# AT89S52.net
KiCad netlist of a schematic drawn in Altium Designer
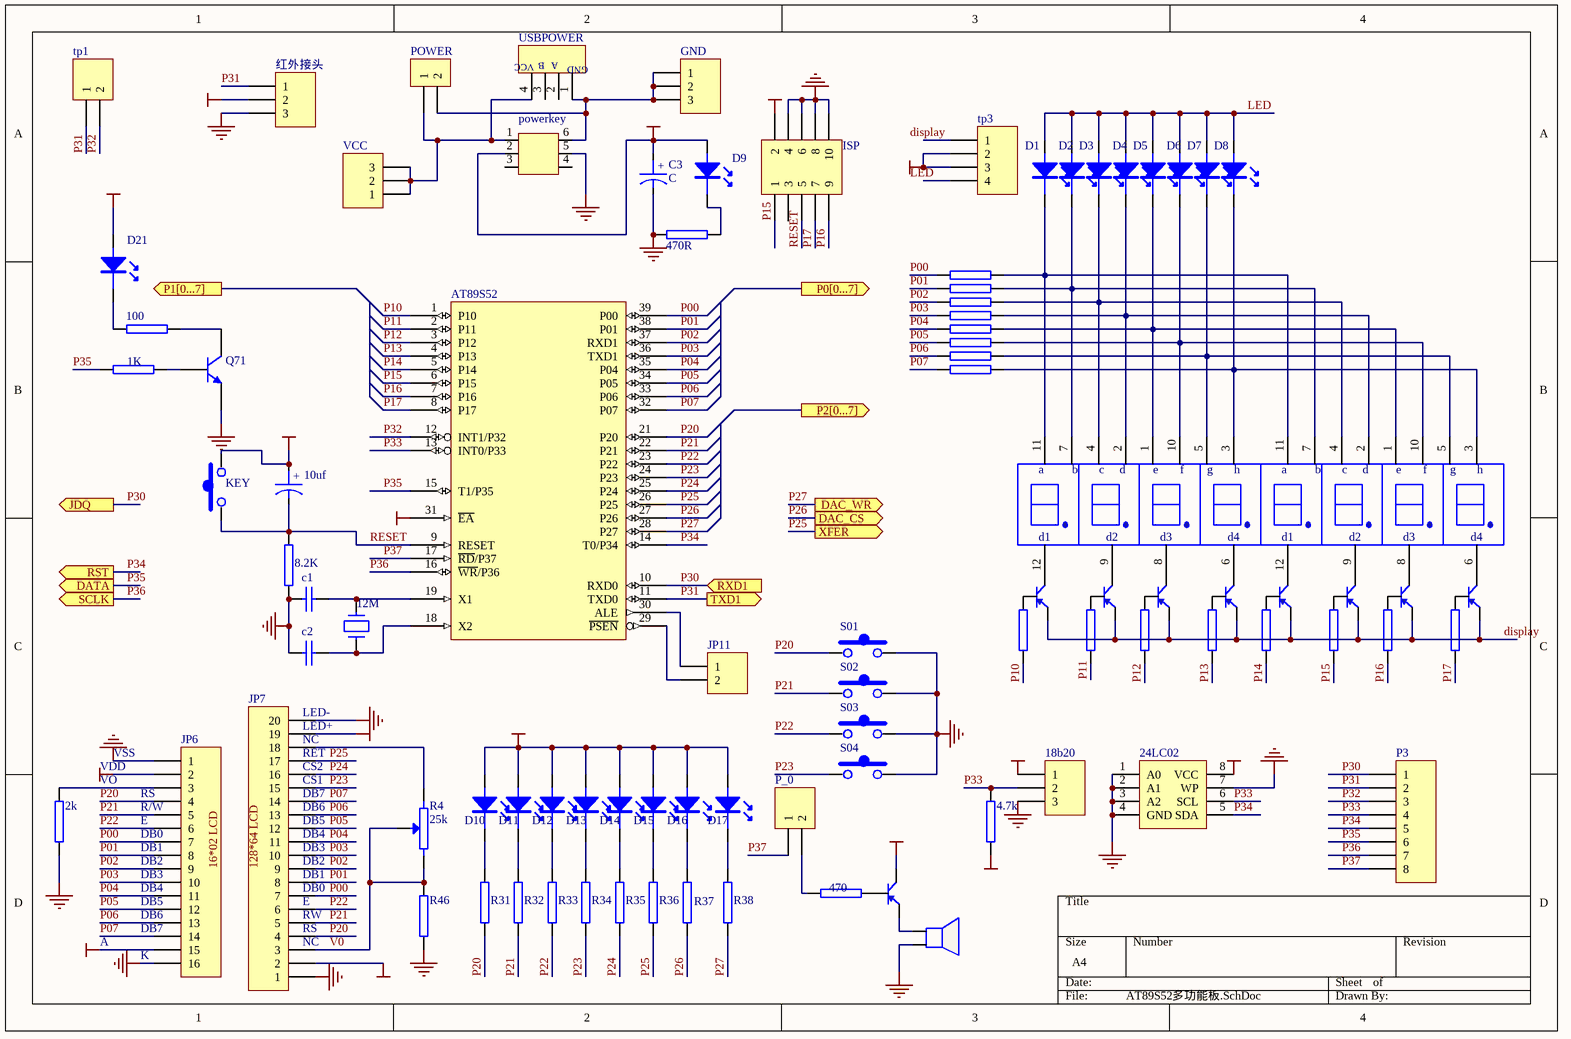
[diagram p0: AT89S52多功能板.SchDoc]

(export (version "E")
  (design (tool "Eeschema 10.0.6"))
  (components
    (comp (ref "*") (value "LS1") (footprint "LS1PF") (libsource (lib "OldCow1 (1)") (part "LS1")))
    (comp (ref "1") (value "NPN1") (footprint "NPN1PF") (libsource (lib "OldCow1 (1)") (part "NPN1")))
    (comp (ref "1K") (value "RES34") (footprint "RES1PF") (libsource (lib "") (part "RES1_1")))
    (comp (ref "2") (value "2") (footprint "NPN1PF") (libsource (lib "OldCow1 (1)") (part "NPN1")))
    (comp (ref "2k") (value "R5") (footprint "RES1PF") (libsource (lib "OldCow1 (1)") (part "RES1")))
    (comp (ref "3") (value "3") (footprint "NPN1PF") (libsource (lib "OldCow1 (1)") (part "NPN1")))
    (comp (ref "4") (value "NPN1") (footprint "NPN1PF") (libsource (lib "OldCow1 (1)") (part "NPN1")))
    (comp (ref "4.7k") (value "RES1") (footprint "RES1PF") (libsource (lib "OldCow1 (1)") (part "RES1")))
    (comp (ref "5") (value "NPN1") (footprint "NPN1PF") (libsource (lib "OldCow1 (1)") (part "NPN1")))
    (comp (ref "6") (value "NPN1") (footprint "NPN1PF") (libsource (lib "OldCow1 (1)") (part "NPN1")))
    (comp (ref "7") (value "NPN1") (footprint "NPN1PF") (libsource (lib "OldCow1 (1)") (part "NPN1")))
    (comp (ref "8") (value "NPN1") (footprint "NPN1PF") (libsource (lib "OldCow1 (1)") (part "NPN1")))
    (comp (ref "8.2K") (value "RES1") (footprint "RES1PF") (libsource (lib "") (part "RES1_1")))
    (comp (ref "10") (value "NPN1") (footprint "NPN1PF") (libsource (lib "OldCow1 (1)") (part "NPN1")))
    (comp (ref "10uf")
      (value "10uf")
      (footprint "cap2")
      (description "Capacitor")
      (libsource (lib "*") (part "CAPACITOR POL"))
    )
    (comp (ref "12M")
      (value "12M")
      (footprint "CRYSTAL")
      (description "Crystal")
      (libsource (lib "*") (part "CRYSTAL"))
    )
    (comp (ref "18b20")
      (value "CON3")
      (footprint "HDR1X3")
      (description "Header, 3-Pin")
      (fields (field (name "PUBLISHER") "Altium Limited"))
      (libsource (lib "Miscellaneous Connectors") (part "Header 3"))
    )
    (comp (ref "24LC02") (value "24LC02") (footprint "DIP8") (libsource (lib "OldCow1 (1)") (part "24LC02")))
    (comp (ref "100") (value "RES2") (footprint "RES1PF") (libsource (lib "") (part "RES1_1")))
    (comp (ref "211")
      (value "USBPOWER")
      (footprint "USBPOWER1")
      (libsource (lib "OldCow1 (1)") (part "USBPOWER"))
    )
    (comp (ref "470") (value "R2") (footprint "RES1PF") (libsource (lib "OldCow1 (1)") (part "RES1")))
    (comp (ref "470R") (value "R1") (footprint "RES1PF") (libsource (lib "OldCow1 (1)") (part "RES1")))
    (comp (ref "1111") (value "LED8") (footprint "LED8PF") (libsource (lib "OldCow1 (1)") (part "LED8")))
    (comp (ref "1112") (value "LED8") (footprint "LED8PF") (libsource (lib "OldCow1 (1)") (part "LED8")))
    (comp (ref "AT89S52")
      (value "AT89S52")
      (footprint "AT89S52PF")
      (libsource (lib "OldCow1 (1)") (part "8051"))
    )
    (comp (ref "c1")
      (value "C")
      (footprint "RAD0.3")
      (description "Capacitor")
      (libsource (lib "*") (part "CAP"))
    )
    (comp (ref "c2")
      (value "15p")
      (footprint "RAD0.3")
      (description "Capacitor")
      (libsource (lib "*") (part "CAP"))
    )
    (comp (ref "C3")
      (value "C")
      (footprint "RAD0.3")
      (description "Capacitor")
      (libsource (lib "OldCow1 (1)") (part "CAPACITOR POL"))
    )
    (comp (ref "D1") (value "LED") (footprint "RES1PF") (libsource (lib "OldCow1 (1)") (part "LED")))
    (comp (ref "D2") (value "LED") (footprint "RES1PF") (libsource (lib "OldCow1 (1)") (part "LED")))
    (comp (ref "D3") (value "LED") (footprint "RES1PF") (libsource (lib "OldCow1 (1)") (part "LED")))
    (comp (ref "D4") (value "LED") (footprint "RES1PF") (libsource (lib "OldCow1 (1)") (part "LED")))
    (comp (ref "D5") (value "LED") (footprint "RES1PF") (libsource (lib "OldCow1 (1)") (part "LED")))
    (comp (ref "D6") (value "LED") (footprint "RES1PF") (libsource (lib "OldCow1 (1)") (part "LED")))
    (comp (ref "D7") (value "LED") (footprint "RES1PF") (libsource (lib "OldCow1 (1)") (part "LED")))
    (comp (ref "D8") (value "LED") (footprint "RES1PF") (libsource (lib "OldCow1 (1)") (part "LED")))
    (comp (ref "D9") (value "LED") (footprint "RES1PF") (libsource (lib "OldCow1 (1)") (part "LED")))
    (comp (ref "D10") (value "LED") (footprint "RES1PF") (libsource (lib "OldCow1 (1)") (part "LED")))
    (comp (ref "D11") (value "LED") (footprint "RES1PF") (libsource (lib "OldCow1 (1)") (part "LED")))
    (comp (ref "D12") (value "LED") (footprint "RES1PF") (libsource (lib "OldCow1 (1)") (part "LED")))
    (comp (ref "D13") (value "LED") (footprint "RES1PF") (libsource (lib "OldCow1 (1)") (part "LED")))
    (comp (ref "D14") (value "LED") (footprint "RES1PF") (libsource (lib "OldCow1 (1)") (part "LED")))
    (comp (ref "D15") (value "LED") (footprint "RES1PF") (libsource (lib "OldCow1 (1)") (part "LED")))
    (comp (ref "D16") (value "LED") (footprint "RES1PF") (libsource (lib "OldCow1 (1)") (part "LED")))
    (comp (ref "D17") (value "LED") (footprint "RES1PF") (libsource (lib "OldCow1 (1)") (part "LED")))
    (comp (ref "D21") (value "LED") (footprint "LED") (libsource (lib "OldCow1 (1)") (part "LED")))
    (comp (ref "GND")
      (value "公共电源")
      (footprint "HDR1X3")
      (description "Header, 3-Pin")
      (fields (field (name "PUBLISHER") "Altium Limited"))
      (libsource (lib "Miscellaneous Connectors") (part "Header 3"))
    )
    (comp (ref "ISP")
      (value "download")
      (footprint "HDR2X5")
      (description "Header, 5-Pin, Dual row")
      (fields (field (name "PUBLISHER") "Altium Limited"))
      (libsource (lib "Miscellaneous Connectors") (part "Header 5X2"))
    )
    (comp (ref "JP6")
      (value "Header 16")
      (footprint "HDR1X16")
      (description "Header, 16-Pin")
      (fields (field (name "PUBLISHER") "Altium Limited"))
      (libsource (lib "Miscellaneous Connectors") (part "Header 16"))
    )
    (comp (ref "JP7")
      (value "~")
      (footprint "HDR1X20")
      (description "Header, 20-Pin")
      (fields (field (name "PUBLISHER") "Altium Limited"))
      (libsource (lib "Miscellaneous Connectors") (part "Header 20"))
    )
    (comp (ref "JP11")
      (value "Header 2")
      (footprint "HDR1X2")
      (description "Header, 2-Pin")
      (fields (field (name "PUBLISHER") "Altium Limited"))
      (libsource (lib "") (part "Header 2_1"))
    )
    (comp (ref "P3")
      (value "Header 8")
      (footprint "HDR1X8")
      (description "Header, 8-Pin")
      (fields (field (name "PUBLISHER") "Altium Limited"))
      (libsource (lib "Miscellaneous Connectors") (part "Header 8"))
    )
    (comp (ref "POWER") (value "POWER") (footprint "POWERPF") (libsource (lib "OldCow1 (1)") (part "POWER")))
    (comp (ref "powerkey")
      (value "POWERKEY")
      (footprint "POWERKEY1")
      (libsource (lib "OldCow1 (1)") (part "POWERKEY"))
    )
    (comp (ref "P_0")
      (value "Header 2")
      (footprint "HDR1X2")
      (description "Header, 2-Pin")
      (fields (field (name "PUBLISHER") "Altium Limited"))
      (libsource (lib "Miscellaneous Connectors") (part "Header 2"))
    )
    (comp (ref "Q71")
      (value "2N3904")
      (footprint "TO-92A")
      (description "NPN General Purpose Amplifier")
      (fields (field (name "PUBLISHER") "Altium Limited"))
      (libsource (lib "Miscellaneous Devices") (part "2N3904"))
    )
    (comp (ref "R4")
      (value "25k")
      (footprint "SIP3-D")
      (description "Potentiometer")
      (libsource (lib "*") (part "POT2"))
    )
    (comp (ref "R11") (value "RES1") (footprint "RES1PF") (libsource (lib "OldCow1 (1)") (part "RES1")))
    (comp (ref "R12") (value "RES1") (footprint "RES1PF") (libsource (lib "OldCow1 (1)") (part "RES1")))
    (comp (ref "R13") (value "RES1") (footprint "RES1PF") (libsource (lib "OldCow1 (1)") (part "RES1")))
    (comp (ref "R14") (value "RES1") (footprint "RES1PF") (libsource (lib "OldCow1 (1)") (part "RES1")))
    (comp (ref "R15") (value "RES1") (footprint "RES1PF") (libsource (lib "OldCow1 (1)") (part "RES1")))
    (comp (ref "R16") (value "RES1") (footprint "RES1PF") (libsource (lib "OldCow1 (1)") (part "RES1")))
    (comp (ref "R17") (value "RES1") (footprint "RES1PF") (libsource (lib "OldCow1 (1)") (part "RES1")))
    (comp (ref "R18") (value "RES1") (footprint "RES1PF") (libsource (lib "OldCow1 (1)") (part "RES1")))
    (comp (ref "R21") (value "RES1") (footprint "RES1PF") (libsource (lib "OldCow1 (1)") (part "RES1")))
    (comp (ref "R22") (value "RES1") (footprint "RES1PF") (libsource (lib "OldCow1 (1)") (part "RES1")))
    (comp (ref "R23") (value "RES1") (footprint "RES1PF") (libsource (lib "OldCow1 (1)") (part "RES1")))
    (comp (ref "R24") (value "RES1") (footprint "RES1PF") (libsource (lib "OldCow1 (1)") (part "RES1")))
    (comp (ref "R25") (value "RES1") (footprint "RES1PF") (libsource (lib "OldCow1 (1)") (part "RES1")))
    (comp (ref "R26") (value "RES1") (footprint "RES1PF") (libsource (lib "OldCow1 (1)") (part "RES1")))
    (comp (ref "R27") (value "RES1") (footprint "RES1PF") (libsource (lib "OldCow1 (1)") (part "RES1")))
    (comp (ref "R28") (value "RES1") (footprint "RES1PF") (libsource (lib "OldCow1 (1)") (part "RES1")))
    (comp (ref "R31") (value "RES1") (footprint "RES1PF") (libsource (lib "") (part "RES1_1")))
    (comp (ref "R32") (value "RES1") (footprint "RES1PF") (libsource (lib "") (part "RES1_1")))
    (comp (ref "R33") (value "RES1") (footprint "RES1PF") (libsource (lib "") (part "RES1_1")))
    (comp (ref "R34") (value "RES1") (footprint "RES1PF") (libsource (lib "") (part "RES1_1")))
    (comp (ref "R35") (value "RES1") (footprint "RES1PF") (libsource (lib "") (part "RES1_1")))
    (comp (ref "R36") (value "RES1") (footprint "RES1PF") (libsource (lib "") (part "RES1_1")))
    (comp (ref "R37") (value "RES1") (footprint "RES1PF") (libsource (lib "") (part "RES1_1")))
    (comp (ref "R38") (value "RES1") (footprint "RES1PF") (libsource (lib "") (part "RES1_1")))
    (comp (ref "R46") (value "RES1") (footprint "RES1PF") (libsource (lib "OldCow1 (1)") (part "RES1")))
    (comp (ref "reset") (value "KEY") (footprint "keypf") (libsource (lib "OldCow1 (1)") (part "KEY")))
    (comp (ref "S01") (value "KEY") (footprint "KEYPF") (libsource (lib "OldCow1 (1)") (part "KEY")))
    (comp (ref "S02") (value "KEY") (footprint "KEYPF") (libsource (lib "OldCow1 (1)") (part "KEY")))
    (comp (ref "S03") (value "KEY") (footprint "KEYPF") (libsource (lib "OldCow1 (1)") (part "KEY")))
    (comp (ref "S04") (value "KEY") (footprint "KEYPF") (libsource (lib "OldCow1 (1)") (part "KEY")))
    (comp (ref "tp1")
      (value "Header 2")
      (footprint "HDR1X2")
      (description "Header, 2-Pin")
      (fields (field (name "PUBLISHER") "Altium Limited"))
      (libsource (lib "Miscellaneous Connectors") (part "Header 2"))
    )
    (comp (ref "tp3")
      (value "Header 4")
      (footprint "HDR1X4")
      (description "Header, 4-Pin")
      (fields (field (name "PUBLISHER") "Altium Limited"))
      (libsource (lib "Miscellaneous Connectors") (part "Header 4"))
    )
    (comp (ref "VCC")
      (value "~")
      (footprint "HDR1X3")
      (description "Header, 3-Pin")
      (fields (field (name "PUBLISHER") "Altium Limited"))
      (libsource (lib "") (part "Header 3_1"))
    )
    (comp (ref "红外接头")
      (value "Header 3")
      (footprint "HDR1X3")
      (description "Header, 3-Pin")
      (fields (field (name "PUBLISHER") "Altium Limited"))
      (libsource (lib "Miscellaneous Connectors") (part "Header 3"))
    )
  )
  (nets
    (net (code "3") (name "/LED") (class "Default")
      (node (ref "D1") (pin "1") (pinfunction "A_1") (pintype "passive"))
      (node (ref "D2") (pin "1") (pinfunction "A_1") (pintype "passive"))
      (node (ref "D3") (pin "1") (pinfunction "A_1") (pintype "passive"))
      (node (ref "D4") (pin "1") (pinfunction "A_1") (pintype "passive"))
      (node (ref "D5") (pin "1") (pinfunction "A_1") (pintype "passive"))
      (node (ref "D6") (pin "1") (pinfunction "A_1") (pintype "passive"))
      (node (ref "D7") (pin "1") (pinfunction "A_1") (pintype "passive"))
      (node (ref "D8") (pin "1") (pinfunction "A_1") (pintype "passive"))
    )
    (net (code "4") (name "/P00") (class "Default")
      (node (ref "AT89S52") (pin "39") (pinfunction "P00_39") (pintype "bidirectional"))
      (node (ref "JP6") (pin "7") (pinfunction "7_7") (pintype "passive"))
      (node (ref "JP7") (pin "7") (pinfunction "7_7") (pintype "passive"))
      (node (ref "R21") (pin "1") (pinfunction "1_1") (pintype "passive"))
    )
    (net (code "6") (name "/P01") (class "Default")
      (node (ref "AT89S52") (pin "38") (pinfunction "P01_38") (pintype "bidirectional"))
      (node (ref "JP6") (pin "8") (pinfunction "8_8") (pintype "passive"))
      (node (ref "JP7") (pin "8") (pinfunction "8_8") (pintype "passive"))
      (node (ref "R22") (pin "1") (pinfunction "1_1") (pintype "passive"))
    )
    (net (code "8") (name "/P02") (class "Default")
      (node (ref "AT89S52") (pin "37") (pinfunction "RXD1_37") (pintype "bidirectional"))
      (node (ref "JP6") (pin "9") (pinfunction "9_9") (pintype "passive"))
      (node (ref "JP7") (pin "9") (pinfunction "9_9") (pintype "passive"))
      (node (ref "R23") (pin "1") (pinfunction "1_1") (pintype "passive"))
    )
    (net (code "10") (name "/P03") (class "Default")
      (node (ref "AT89S52") (pin "36") (pinfunction "TXD1_36") (pintype "bidirectional"))
      (node (ref "JP6") (pin "10") (pinfunction "10_10") (pintype "passive"))
      (node (ref "JP7") (pin "10") (pinfunction "10_10") (pintype "passive"))
      (node (ref "R24") (pin "1") (pinfunction "1_1") (pintype "passive"))
    )
    (net (code "11") (name "/P04") (class "Default")
      (node (ref "AT89S52") (pin "35") (pinfunction "P04_35") (pintype "bidirectional"))
      (node (ref "JP6") (pin "11") (pinfunction "11_11") (pintype "passive"))
      (node (ref "JP7") (pin "11") (pinfunction "11_11") (pintype "passive"))
      (node (ref "R25") (pin "1") (pinfunction "1_1") (pintype "passive"))
    )
    (net (code "12") (name "/P05") (class "Default")
      (node (ref "AT89S52") (pin "34") (pinfunction "P05_34") (pintype "bidirectional"))
      (node (ref "JP6") (pin "12") (pinfunction "12_12") (pintype "passive"))
      (node (ref "JP7") (pin "12") (pinfunction "12_12") (pintype "passive"))
      (node (ref "R26") (pin "1") (pinfunction "1_1") (pintype "passive"))
    )
    (net (code "13") (name "/P06") (class "Default")
      (node (ref "AT89S52") (pin "33") (pinfunction "P06_33") (pintype "bidirectional"))
      (node (ref "JP6") (pin "13") (pinfunction "13_13") (pintype "passive"))
      (node (ref "JP7") (pin "13") (pinfunction "13_13") (pintype "passive"))
      (node (ref "R27") (pin "1") (pinfunction "1_1") (pintype "passive"))
    )
    (net (code "14") (name "/P07") (class "Default")
      (node (ref "AT89S52") (pin "32") (pinfunction "P07_32") (pintype "bidirectional"))
      (node (ref "JP6") (pin "14") (pinfunction "14_14") (pintype "passive"))
      (node (ref "JP7") (pin "14") (pinfunction "14_14") (pintype "passive"))
      (node (ref "R28") (pin "1") (pinfunction "1_1") (pintype "passive"))
    )
    (net (code "15") (name "/P10") (class "Default")
      (node (ref "AT89S52") (pin "1") (pinfunction "P10_1") (pintype "bidirectional"))
      (node (ref "R11") (pin "1") (pinfunction "1_1") (pintype "passive"))
    )
    (net (code "16") (name "/P11") (class "Default")
      (node (ref "AT89S52") (pin "2") (pinfunction "P11_2") (pintype "bidirectional"))
      (node (ref "R12") (pin "1") (pinfunction "1_1") (pintype "passive"))
    )
    (net (code "17") (name "/P12") (class "Default")
      (node (ref "AT89S52") (pin "3") (pinfunction "P12_3") (pintype "bidirectional"))
      (node (ref "R13") (pin "1") (pinfunction "1_1") (pintype "passive"))
    )
    (net (code "18") (name "/P13") (class "Default")
      (node (ref "AT89S52") (pin "4") (pinfunction "P13_4") (pintype "bidirectional"))
      (node (ref "R14") (pin "1") (pinfunction "1_1") (pintype "passive"))
    )
    (net (code "19") (name "/P14") (class "Default")
      (node (ref "AT89S52") (pin "5") (pinfunction "P14_5") (pintype "bidirectional"))
      (node (ref "R15") (pin "1") (pinfunction "1_1") (pintype "passive"))
    )
    (net (code "20") (name "/P15") (class "Default")
      (node (ref "AT89S52") (pin "6") (pinfunction "P15_6") (pintype "bidirectional"))
      (node (ref "ISP") (pin "1") (pinfunction "1_1") (pintype "passive"))
      (node (ref "R16") (pin "1") (pinfunction "1_1") (pintype "passive"))
    )
    (net (code "21") (name "/P16") (class "Default")
      (node (ref "AT89S52") (pin "7") (pinfunction "P16_7") (pintype "bidirectional"))
      (node (ref "ISP") (pin "9") (pinfunction "9_9") (pintype "passive"))
      (node (ref "R17") (pin "1") (pinfunction "1_1") (pintype "passive"))
    )
    (net (code "22") (name "/P17") (class "Default")
      (node (ref "AT89S52") (pin "8") (pinfunction "P17_8") (pintype "bidirectional"))
      (node (ref "ISP") (pin "7") (pinfunction "7_7") (pintype "passive"))
      (node (ref "R18") (pin "1") (pinfunction "1_1") (pintype "passive"))
    )
    (net (code "23") (name "/P20") (class "Default")
      (node (ref "AT89S52") (pin "21") (pinfunction "P20_21") (pintype "bidirectional"))
      (node (ref "JP6") (pin "4") (pinfunction "4_4") (pintype "passive"))
      (node (ref "JP7") (pin "4") (pinfunction "4_4") (pintype "passive"))
      (node (ref "R31") (pin "1") (pinfunction "1_1") (pintype "passive"))
      (node (ref "S01") (pin "1") (pinfunction "1_1") (pintype "passive"))
    )
    (net (code "24") (name "/P21") (class "Default")
      (node (ref "AT89S52") (pin "22") (pinfunction "P21_22") (pintype "bidirectional"))
      (node (ref "JP6") (pin "5") (pinfunction "5_5") (pintype "passive"))
      (node (ref "JP7") (pin "5") (pinfunction "5_5") (pintype "passive"))
      (node (ref "R32") (pin "1") (pinfunction "1_1") (pintype "passive"))
      (node (ref "S02") (pin "1") (pinfunction "1_1") (pintype "passive"))
    )
    (net (code "25") (name "/P22") (class "Default")
      (node (ref "AT89S52") (pin "23") (pinfunction "P22_23") (pintype "bidirectional"))
      (node (ref "JP6") (pin "6") (pinfunction "6_6") (pintype "passive"))
      (node (ref "JP7") (pin "6") (pinfunction "6_6") (pintype "passive"))
      (node (ref "R33") (pin "1") (pinfunction "1_1") (pintype "passive"))
      (node (ref "S03") (pin "1") (pinfunction "1_1") (pintype "passive"))
    )
    (net (code "26") (name "/P23") (class "Default")
      (node (ref "AT89S52") (pin "24") (pinfunction "P23_24") (pintype "bidirectional"))
      (node (ref "JP7") (pin "15") (pinfunction "15_15") (pintype "passive"))
      (node (ref "R34") (pin "1") (pinfunction "1_1") (pintype "passive"))
      (node (ref "S04") (pin "1") (pinfunction "1_1") (pintype "passive"))
    )
    (net (code "27") (name "/P24") (class "Default")
      (node (ref "AT89S52") (pin "25") (pinfunction "P24_25") (pintype "bidirectional"))
      (node (ref "JP7") (pin "16") (pinfunction "16_16") (pintype "passive"))
      (node (ref "R35") (pin "1") (pinfunction "1_1") (pintype "passive"))
    )
    (net (code "28") (name "/P25") (class "Default")
      (node (ref "AT89S52") (pin "26") (pinfunction "P25_26") (pintype "bidirectional"))
      (node (ref "JP7") (pin "17") (pinfunction "17_17") (pintype "passive"))
      (node (ref "R36") (pin "1") (pinfunction "1_1") (pintype "passive"))
    )
    (net (code "29") (name "/P26") (class "Default")
      (node (ref "AT89S52") (pin "27") (pinfunction "P26_27") (pintype "bidirectional"))
      (node (ref "R37") (pin "1") (pinfunction "1_1") (pintype "passive"))
    )
    (net (code "30") (name "/P27") (class "Default")
      (node (ref "AT89S52") (pin "28") (pinfunction "P27_28") (pintype "bidirectional"))
      (node (ref "R38") (pin "1") (pinfunction "1_1") (pintype "passive"))
    )
    (net (code "31") (name "/P30") (class "Default")
      (node (ref "AT89S52") (pin "10") (pinfunction "RXD0_10") (pintype "bidirectional"))
      (node (ref "P3") (pin "1") (pinfunction "1_1") (pintype "passive"))
    )
    (net (code "32") (name "/P31") (class "Default")
      (node (ref "AT89S52") (pin "11") (pinfunction "TXD0_11") (pintype "bidirectional"))
      (node (ref "P3") (pin "2") (pinfunction "2_2") (pintype "passive"))
      (node (ref "tp1") (pin "1") (pinfunction "1_1") (pintype "passive"))
      (node (ref "红外接头") (pin "1") (pinfunction "1_1") (pintype "passive"))
    )
    (net (code "33") (name "/P32") (class "Default")
      (node (ref "AT89S52") (pin "12") (pinfunction "INT1/P32_12") (pintype "bidirectional"))
      (node (ref "P3") (pin "3") (pinfunction "3_3") (pintype "passive"))
      (node (ref "tp1") (pin "2") (pinfunction "2_2") (pintype "passive"))
    )
    (net (code "34") (name "/P33") (class "Default")
      (node (ref "18b20") (pin "2") (pinfunction "2_2") (pintype "passive"))
      (node (ref "24LC02") (pin "6") (pinfunction "SCL_6") (pintype "passive"))
      (node (ref "4.7k") (pin "2") (pinfunction "2_2") (pintype "passive"))
      (node (ref "AT89S52") (pin "13") (pinfunction "INT0/P33_13") (pintype "bidirectional"))
      (node (ref "P3") (pin "4") (pinfunction "4_4") (pintype "passive"))
    )
    (net (code "35") (name "/P34") (class "Default")
      (node (ref "24LC02") (pin "5") (pinfunction "SDA_5") (pintype "passive"))
      (node (ref "AT89S52") (pin "14") (pinfunction "T0/P34_14") (pintype "bidirectional"))
      (node (ref "P3") (pin "5") (pinfunction "5_5") (pintype "passive"))
    )
    (net (code "36") (name "/P35") (class "Default")
      (node (ref "1K") (pin "1") (pinfunction "1_1") (pintype "passive"))
      (node (ref "AT89S52") (pin "15") (pinfunction "T1/P35_15") (pintype "bidirectional"))
      (node (ref "P3") (pin "6") (pinfunction "6_6") (pintype "passive"))
    )
    (net (code "37") (name "/P36") (class "Default")
      (node (ref "AT89S52") (pin "16") (pinfunction "~{WR}/P36_16") (pintype "bidirectional"))
      (node (ref "P3") (pin "7") (pinfunction "7_7") (pintype "passive"))
    )
    (net (code "38") (name "/P37") (class "Default")
      (node (ref "AT89S52") (pin "17") (pinfunction "~{RD}/P37_17") (pintype "input"))
      (node (ref "P3") (pin "8") (pinfunction "8_8") (pintype "passive"))
      (node (ref "P_0") (pin "1") (pinfunction "1_1") (pintype "passive"))
    )
    (net (code "39") (name "/RESET") (class "Default")
      (node (ref "10uf") (pin "2") (pinfunction "2_2") (pintype "passive"))
      (node (ref "8.2K") (pin "1") (pinfunction "1_1") (pintype "passive"))
      (node (ref "AT89S52") (pin "9") (pinfunction "RESET_9") (pintype "input"))
      (node (ref "ISP") (pin "5") (pinfunction "5_5") (pintype "passive"))
      (node (ref "reset") (pin "1") (pinfunction "1_1") (pintype "passive"))
    )
    (net (code "40") (name "/V0") (class "Default")
      (node (ref "JP7") (pin "3") (pinfunction "3_3") (pintype "passive"))
      (node (ref "R4") (pin "1") (pinfunction "1_1") (pintype "passive"))
      (node (ref "R4") (pin "3") (pinfunction "W_3") (pintype "passive"))
      (node (ref "R46") (pin "2") (pinfunction "2_2") (pintype "passive"))
    )
    (net (code "41") (name "/display") (class "Default")
      (node (ref "1") (pin "e") (pinfunction "1_e") (pintype "passive"))
      (node (ref "2") (pin "e") (pinfunction "1_e") (pintype "passive"))
      (node (ref "3") (pin "e") (pinfunction "1_e") (pintype "passive"))
      (node (ref "4") (pin "e") (pinfunction "1_e") (pintype "passive"))
      (node (ref "5") (pin "e") (pinfunction "1_e") (pintype "passive"))
      (node (ref "6") (pin "e") (pinfunction "1_e") (pintype "passive"))
      (node (ref "7") (pin "e") (pinfunction "1_e") (pintype "passive"))
      (node (ref "8") (pin "e") (pinfunction "1_e") (pintype "passive"))
    )
    (net (code "42") (name "GND") (class "Default")
      (node (ref "*") (pin "2") (pinfunction "2_2") (pintype "passive"))
      (node (ref "18b20") (pin "3") (pinfunction "3_3") (pintype "passive"))
      (node (ref "24LC02") (pin "1") (pinfunction "A0_1") (pintype "passive"))
      (node (ref "24LC02") (pin "2") (pinfunction "A1_2") (pintype "passive"))
      (node (ref "24LC02") (pin "3") (pinfunction "A2_3") (pintype "passive"))
      (node (ref "24LC02") (pin "4") (pinfunction "GND_4") (pintype "passive"))
      (node (ref "24LC02") (pin "7") (pinfunction "WP_7") (pintype "passive"))
      (node (ref "2k") (pin "1") (pinfunction "1_1") (pintype "passive"))
      (node (ref "470R") (pin "2") (pinfunction "2_2") (pintype "passive"))
      (node (ref "8.2K") (pin "2") (pinfunction "2_2") (pintype "passive"))
      (node (ref "AT89S52") (pin "20") (pinfunction "GND_20") (pintype "power_in"))
      (node (ref "C3") (pin "2") (pinfunction "2_2") (pintype "passive"))
      (node (ref "ISP") (pin "10") (pinfunction "10_10") (pintype "passive"))
      (node (ref "ISP") (pin "4") (pinfunction "4_4") (pintype "passive"))
      (node (ref "ISP") (pin "6") (pinfunction "6_6") (pintype "passive"))
      (node (ref "ISP") (pin "8") (pinfunction "8_8") (pintype "passive"))
      (node (ref "JP6") (pin "1") (pinfunction "1_1") (pintype "passive"))
      (node (ref "JP6") (pin "16") (pinfunction "16_16") (pintype "passive"))
      (node (ref "JP7") (pin "1") (pinfunction "1_1") (pintype "passive"))
      (node (ref "JP7") (pin "20") (pinfunction "20_20") (pintype "passive"))
      (node (ref "Q71") (pin "1") (pinfunction "E_1") (pintype "passive"))
      (node (ref "R46") (pin "1") (pinfunction "1_1") (pintype "passive"))
      (node (ref "S01") (pin "2") (pinfunction "2_2") (pintype "passive"))
      (node (ref "S02") (pin "2") (pinfunction "2_2") (pintype "passive"))
      (node (ref "S03") (pin "2") (pinfunction "2_2") (pintype "passive"))
      (node (ref "S04") (pin "2") (pinfunction "2_2") (pintype "passive"))
      (node (ref "c1") (pin "1") (pinfunction "1_1") (pintype "passive"))
      (node (ref "c2") (pin "1") (pinfunction "1_1") (pintype "passive"))
      (node (ref "powerkey") (pin "5") (pinfunction "5_5") (pintype "passive"))
      (node (ref "红外接头") (pin "3") (pinfunction "3_3") (pintype "passive"))
    )
    (net (code "43") (name "Net-(1-2)") (class "Default")
      (node (ref "1") (pin "b") (pinfunction "2_b") (pintype "passive"))
      (node (ref "R11") (pin "2") (pinfunction "2_2") (pintype "passive"))
    )
    (net (code "44") (name "Net-(1-3)") (class "Default")
      (node (ref "1") (pin "c") (pinfunction "3_c") (pintype "passive"))
      (node (ref "1112") (pin "12") (pinfunction "d1_12") (pintype "passive"))
    )
    (net (code "45") (name "Net-(2-2)") (class "Default")
      (node (ref "2") (pin "b") (pinfunction "2_b") (pintype "passive"))
      (node (ref "R12") (pin "2") (pinfunction "2_2") (pintype "passive"))
    )
    (net (code "46") (name "Net-(2-3)") (class "Default")
      (node (ref "1112") (pin "9") (pinfunction "5_9") (pintype "passive"))
      (node (ref "2") (pin "c") (pinfunction "3_c") (pintype "passive"))
    )
    (net (code "47") (name "Net-(2k-Pad2)") (class "Default")
      (node (ref "2k") (pin "2") (pinfunction "2_2") (pintype "passive"))
      (node (ref "JP6") (pin "3") (pinfunction "3_3") (pintype "passive"))
    )
    (net (code "48") (name "Net-(3-2)") (class "Default")
      (node (ref "3") (pin "b") (pinfunction "2_b") (pintype "passive"))
      (node (ref "R13") (pin "2") (pinfunction "2_2") (pintype "passive"))
    )
    (net (code "49") (name "Net-(3-3)") (class "Default")
      (node (ref "1112") (pin "8") (pinfunction "6_8") (pintype "passive"))
      (node (ref "3") (pin "c") (pinfunction "3_c") (pintype "passive"))
    )
    (net (code "50") (name "Net-(4-2)") (class "Default")
      (node (ref "4") (pin "b") (pinfunction "2_b") (pintype "passive"))
      (node (ref "R14") (pin "2") (pinfunction "2_2") (pintype "passive"))
    )
    (net (code "51") (name "Net-(4-3)") (class "Default")
      (node (ref "1112") (pin "6") (pinfunction "6_6") (pintype "passive"))
      (node (ref "4") (pin "c") (pinfunction "3_c") (pintype "passive"))
    )
    (net (code "52") (name "Net-(5-2)") (class "Default")
      (node (ref "5") (pin "b") (pinfunction "2_b") (pintype "passive"))
      (node (ref "R15") (pin "2") (pinfunction "2_2") (pintype "passive"))
    )
    (net (code "53") (name "Net-(6-2)") (class "Default")
      (node (ref "6") (pin "b") (pinfunction "2_b") (pintype "passive"))
      (node (ref "R16") (pin "2") (pinfunction "2_2") (pintype "passive"))
    )
    (net (code "54") (name "Net-(6-3)") (class "Default")
      (node (ref "1111") (pin "9") (pinfunction "5_9") (pintype "passive"))
      (node (ref "6") (pin "c") (pinfunction "3_c") (pintype "passive"))
    )
    (net (code "55") (name "Net-(7-2)") (class "Default")
      (node (ref "7") (pin "b") (pinfunction "2_b") (pintype "passive"))
      (node (ref "R17") (pin "2") (pinfunction "2_2") (pintype "passive"))
    )
    (net (code "56") (name "Net-(7-3)") (class "Default")
      (node (ref "1111") (pin "8") (pinfunction "6_8") (pintype "passive"))
      (node (ref "7") (pin "c") (pinfunction "3_c") (pintype "passive"))
    )
    (net (code "57") (name "Net-(8-2)") (class "Default")
      (node (ref "8") (pin "b") (pinfunction "2_b") (pintype "passive"))
      (node (ref "R18") (pin "2") (pinfunction "2_2") (pintype "passive"))
    )
    (net (code "58") (name "Net-(8-3)") (class "Default")
      (node (ref "1111") (pin "6") (pinfunction "6_6") (pintype "passive"))
      (node (ref "8") (pin "c") (pinfunction "3_c") (pintype "passive"))
    )
    (net (code "59") (name "Net-(10-1)") (class "Default")
      (node (ref "*") (pin "1") (pinfunction "1_1") (pintype "passive"))
      (node (ref "10") (pin "e") (pinfunction "1_e") (pintype "passive"))
    )
    (net (code "60") (name "Net-(10-2)") (class "Default")
      (node (ref "10") (pin "b") (pinfunction "2_b") (pintype "passive"))
      (node (ref "470") (pin "1") (pinfunction "1_1") (pintype "passive"))
    )
    (net (code "61") (name "Net-(211-3)") (class "Default")
      (node (ref "211") (pin "4") (pinfunction "3_4") (pintype "passive"))
      (node (ref "POWER") (pin "1") (pinfunction "1_1") (pintype "passive"))
      (node (ref "VCC") (pin "1") (pinfunction "1_1") (pintype "passive"))
      (node (ref "VCC") (pin "2") (pinfunction "2_2") (pintype "passive"))
      (node (ref "VCC") (pin "3") (pinfunction "3_3") (pintype "passive"))
      (node (ref "powerkey") (pin "1") (pinfunction "1_1") (pintype "passive"))
    )
    (net (code "62") (name "Net-(211-VCC)") (class "Default")
      (node (ref "211") (pin "1") (pinfunction "VCC_1") (pintype "passive"))
      (node (ref "GND") (pin "1") (pinfunction "1_1") (pintype "passive"))
      (node (ref "GND") (pin "2") (pinfunction "2_2") (pintype "passive"))
      (node (ref "GND") (pin "3") (pinfunction "3_3") (pintype "passive"))
      (node (ref "POWER") (pin "2") (pinfunction "2_2") (pintype "passive"))
      (node (ref "powerkey") (pin "6") (pinfunction "6_6") (pintype "passive"))
    )
    (net (code "63") (name "Net-(470-Pad2)") (class "Default")
      (node (ref "470") (pin "2") (pinfunction "2_2") (pintype "passive"))
      (node (ref "P_0") (pin "2") (pinfunction "2_2") (pintype "passive"))
    )
    (net (code "64") (name "Net-(1111-d1)") (class "Default")
      (node (ref "1111") (pin "12") (pinfunction "d1_12") (pintype "passive"))
      (node (ref "5") (pin "c") (pinfunction "3_c") (pintype "passive"))
    )
    (net (code "65") (name "Net-(AT89S52-ALE)") (class "Default")
      (node (ref "AT89S52") (pin "30") (pinfunction "ALE_30") (pintype "output"))
      (node (ref "JP11") (pin "1") (pinfunction "1_1") (pintype "passive"))
    )
    (net (code "66") (name "Net-(AT89S52-X1)") (class "Default")
      (node (ref "12M") (pin "1") (pinfunction "1_1") (pintype "passive"))
      (node (ref "AT89S52") (pin "19") (pinfunction "X1_19") (pintype "input"))
      (node (ref "c1") (pin "2") (pinfunction "2_2") (pintype "passive"))
    )
    (net (code "67") (name "Net-(AT89S52-X2)") (class "Default")
      (node (ref "12M") (pin "2") (pinfunction "2_2") (pintype "passive"))
      (node (ref "AT89S52") (pin "18") (pinfunction "X2_18") (pintype "input"))
      (node (ref "c2") (pin "2") (pinfunction "2_2") (pintype "passive"))
    )
    (net (code "68") (name "Net-(AT89S52-~{PSEN})") (class "Default")
      (node (ref "AT89S52") (pin "29") (pinfunction "~{PSEN}_29") (pintype "output"))
      (node (ref "JP11") (pin "2") (pinfunction "2_2") (pintype "passive"))
    )
    (net (code "69") (name "Net-(D1-K)") (class "Default")
      (node (ref "1111") (pin "11") (pinfunction "11_11") (pintype "passive"))
      (node (ref "1112") (pin "11") (pinfunction "11_11") (pintype "passive"))
      (node (ref "D1") (pin "2") (pinfunction "K_2") (pintype "passive"))
      (node (ref "R21") (pin "2") (pinfunction "2_2") (pintype "passive"))
    )
    (net (code "70") (name "Net-(D2-K)") (class "Default")
      (node (ref "1111") (pin "7") (pinfunction "7_7") (pintype "passive"))
      (node (ref "1112") (pin "7") (pinfunction "7_7") (pintype "passive"))
      (node (ref "D2") (pin "2") (pinfunction "K_2") (pintype "passive"))
      (node (ref "R22") (pin "2") (pinfunction "2_2") (pintype "passive"))
    )
    (net (code "71") (name "Net-(D3-K)") (class "Default")
      (node (ref "1111") (pin "4") (pinfunction "4_4") (pintype "passive"))
      (node (ref "1112") (pin "4") (pinfunction "4_4") (pintype "passive"))
      (node (ref "D3") (pin "2") (pinfunction "K_2") (pintype "passive"))
      (node (ref "R23") (pin "2") (pinfunction "2_2") (pintype "passive"))
    )
    (net (code "72") (name "Net-(D4-K)") (class "Default")
      (node (ref "1111") (pin "2") (pinfunction "2_2") (pintype "passive"))
      (node (ref "1112") (pin "2") (pinfunction "2_2") (pintype "passive"))
      (node (ref "D4") (pin "2") (pinfunction "K_2") (pintype "passive"))
      (node (ref "R24") (pin "2") (pinfunction "2_2") (pintype "passive"))
    )
    (net (code "73") (name "Net-(D5-K)") (class "Default")
      (node (ref "1111") (pin "1") (pinfunction "1_1") (pintype "passive"))
      (node (ref "1112") (pin "1") (pinfunction "1_1") (pintype "passive"))
      (node (ref "D5") (pin "2") (pinfunction "K_2") (pintype "passive"))
      (node (ref "R25") (pin "2") (pinfunction "2_2") (pintype "passive"))
    )
    (net (code "74") (name "Net-(D6-K)") (class "Default")
      (node (ref "1111") (pin "10") (pinfunction "10_10") (pintype "passive"))
      (node (ref "1112") (pin "10") (pinfunction "10_10") (pintype "passive"))
      (node (ref "D6") (pin "2") (pinfunction "K_2") (pintype "passive"))
      (node (ref "R26") (pin "2") (pinfunction "2_2") (pintype "passive"))
    )
    (net (code "75") (name "Net-(D7-K)") (class "Default")
      (node (ref "1111") (pin "5") (pinfunction "5_5") (pintype "passive"))
      (node (ref "1112") (pin "5") (pinfunction "5_5") (pintype "passive"))
      (node (ref "D7") (pin "2") (pinfunction "K_2") (pintype "passive"))
      (node (ref "R27") (pin "2") (pinfunction "2_2") (pintype "passive"))
    )
    (net (code "76") (name "Net-(D8-K)") (class "Default")
      (node (ref "1111") (pin "3") (pinfunction "3_3") (pintype "passive"))
      (node (ref "1112") (pin "3") (pinfunction "3_3") (pintype "passive"))
      (node (ref "D8") (pin "2") (pinfunction "K_2") (pintype "passive"))
      (node (ref "R28") (pin "2") (pinfunction "2_2") (pintype "passive"))
    )
    (net (code "77") (name "Net-(D9-K)") (class "Default")
      (node (ref "470R") (pin "1") (pinfunction "1_1") (pintype "passive"))
      (node (ref "D9") (pin "2") (pinfunction "K_2") (pintype "passive"))
    )
    (net (code "78") (name "Net-(D10-K)") (class "Default")
      (node (ref "D10") (pin "2") (pinfunction "K_2") (pintype "passive"))
      (node (ref "R31") (pin "2") (pinfunction "2_2") (pintype "passive"))
    )
    (net (code "79") (name "Net-(D11-K)") (class "Default")
      (node (ref "D11") (pin "2") (pinfunction "K_2") (pintype "passive"))
      (node (ref "R32") (pin "2") (pinfunction "2_2") (pintype "passive"))
    )
    (net (code "80") (name "Net-(D12-K)") (class "Default")
      (node (ref "D12") (pin "2") (pinfunction "K_2") (pintype "passive"))
      (node (ref "R33") (pin "2") (pinfunction "2_2") (pintype "passive"))
    )
    (net (code "81") (name "Net-(D13-K)") (class "Default")
      (node (ref "D13") (pin "2") (pinfunction "K_2") (pintype "passive"))
      (node (ref "R34") (pin "2") (pinfunction "2_2") (pintype "passive"))
    )
    (net (code "82") (name "Net-(D14-K)") (class "Default")
      (node (ref "D14") (pin "2") (pinfunction "K_2") (pintype "passive"))
      (node (ref "R35") (pin "2") (pinfunction "2_2") (pintype "passive"))
    )
    (net (code "83") (name "Net-(D15-K)") (class "Default")
      (node (ref "D15") (pin "2") (pinfunction "K_2") (pintype "passive"))
      (node (ref "R36") (pin "2") (pinfunction "2_2") (pintype "passive"))
    )
    (net (code "84") (name "Net-(D16-K)") (class "Default")
      (node (ref "D16") (pin "2") (pinfunction "K_2") (pintype "passive"))
      (node (ref "R37") (pin "2") (pinfunction "2_2") (pintype "passive"))
    )
    (net (code "85") (name "Net-(D17-K)") (class "Default")
      (node (ref "D17") (pin "2") (pinfunction "K_2") (pintype "passive"))
      (node (ref "R38") (pin "2") (pinfunction "2_2") (pintype "passive"))
    )
    (net (code "86") (name "Net-(D21-K)") (class "Default")
      (node (ref "100") (pin "1") (pinfunction "1_1") (pintype "passive"))
      (node (ref "D21") (pin "2") (pinfunction "K_2") (pintype "passive"))
    )
    (net (code "87") (name "Net-(JP7-Pad18)") (class "Default")
      (node (ref "JP7") (pin "18") (pinfunction "18_18") (pintype "passive"))
      (node (ref "R4") (pin "2") (pinfunction "2_2") (pintype "passive"))
    )
    (net (code "88") (name "Net-(Q71-B)") (class "Default")
      (node (ref "1K") (pin "2") (pinfunction "2_2") (pintype "passive"))
      (node (ref "Q71") (pin "2") (pinfunction "B_2") (pintype "passive"))
    )
    (net (code "89") (name "Net-(Q71-C)") (class "Default")
      (node (ref "100") (pin "2") (pinfunction "2_2") (pintype "passive"))
      (node (ref "Q71") (pin "3") (pinfunction "C_3") (pintype "passive"))
    )
    (net (code "90") (name "VCC") (class "Default")
      (node (ref "10") (pin "c") (pinfunction "3_c") (pintype "passive"))
      (node (ref "10uf") (pin "1") (pinfunction "1_1") (pintype "passive"))
      (node (ref "18b20") (pin "1") (pinfunction "1_1") (pintype "passive"))
      (node (ref "24LC02") (pin "8") (pinfunction "VCC_8") (pintype "passive"))
      (node (ref "4.7k") (pin "1") (pinfunction "1_1") (pintype "passive"))
      (node (ref "AT89S52") (pin "31") (pinfunction "~{EA}_31") (pintype "input"))
      (node (ref "AT89S52") (pin "40") (pinfunction "VCC_40") (pintype "power_in"))
      (node (ref "C3") (pin "1") (pinfunction "1_1") (pintype "passive"))
      (node (ref "D10") (pin "1") (pinfunction "A_1") (pintype "passive"))
      (node (ref "D11") (pin "1") (pinfunction "A_1") (pintype "passive"))
      (node (ref "D12") (pin "1") (pinfunction "A_1") (pintype "passive"))
      (node (ref "D13") (pin "1") (pinfunction "A_1") (pintype "passive"))
      (node (ref "D14") (pin "1") (pinfunction "A_1") (pintype "passive"))
      (node (ref "D15") (pin "1") (pinfunction "A_1") (pintype "passive"))
      (node (ref "D16") (pin "1") (pinfunction "A_1") (pintype "passive"))
      (node (ref "D17") (pin "1") (pinfunction "A_1") (pintype "passive"))
      (node (ref "D21") (pin "1") (pinfunction "A_1") (pintype "passive"))
      (node (ref "D9") (pin "1") (pinfunction "A_1") (pintype "passive"))
      (node (ref "ISP") (pin "2") (pinfunction "2_2") (pintype "passive"))
      (node (ref "JP6") (pin "15") (pinfunction "15_15") (pintype "passive"))
      (node (ref "JP6") (pin "2") (pinfunction "2_2") (pintype "passive"))
      (node (ref "JP7") (pin "19") (pinfunction "19_19") (pintype "passive"))
      (node (ref "JP7") (pin "2") (pinfunction "2_2") (pintype "passive"))
      (node (ref "powerkey") (pin "2") (pinfunction "2_2") (pintype "passive"))
      (node (ref "reset") (pin "2") (pinfunction "2_2") (pintype "passive"))
      (node (ref "tp3") (pin "2") (pinfunction "2_2") (pintype "passive"))
      (node (ref "tp3") (pin "3") (pinfunction "3_3") (pintype "passive"))
      (node (ref "红外接头") (pin "2") (pinfunction "2_2") (pintype "passive"))
    )
    (net (code "91") (name "unconnected-(211-2-Pad3)") (class "Default")
      (node (ref "211") (pin "3") (pinfunction "2_3") (pintype "passive"))
    )
    (net (code "92") (name "unconnected-(211-Pad2)") (class "Default")
      (node (ref "211") (pin "2") (pinfunction "2_2") (pintype "passive"))
    )
    (net (code "93") (name "unconnected-(ISP-Pad3)") (class "Default")
      (node (ref "ISP") (pin "3") (pinfunction "3_3") (pintype "passive"))
    )
    (net (code "94") (name "unconnected-(powerkey-Pad3)") (class "Default")
      (node (ref "powerkey") (pin "3") (pinfunction "3_3") (pintype "passive"))
    )
    (net (code "95") (name "unconnected-(powerkey-Pad4)") (class "Default")
      (node (ref "powerkey") (pin "4") (pinfunction "4_4") (pintype "passive"))
    )
    (net (code "96") (name "unconnected-(tp3-Pad1)") (class "Default")
      (node (ref "tp3") (pin "1") (pinfunction "1_1") (pintype "passive"))
    )
    (net (code "97") (name "unconnected-(tp3-Pad4)") (class "Default")
      (node (ref "tp3") (pin "4") (pinfunction "4_4") (pintype "passive"))
    )
  )
)
